# 22-eDP.net
KiCad netlist of a schematic drawn in Altium Designer
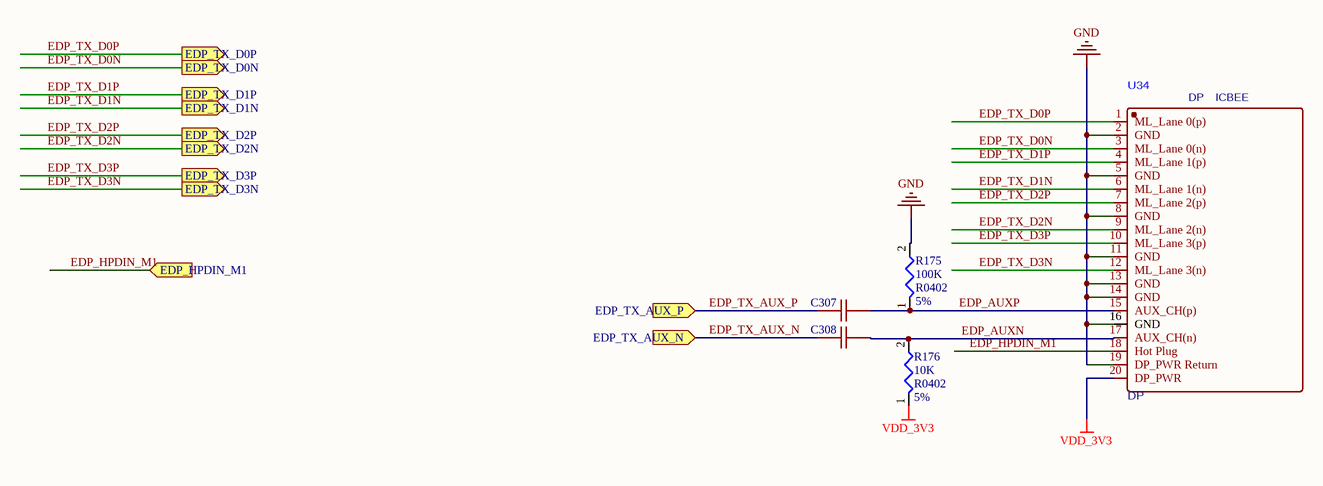
[diagram p0: 22-eDP.SchDoc]

(export (version "E")
  (design (tool "Eeschema 10.0.6"))
  (components
    (comp (ref "C307")
      (value "100nF")
      (footprint "C0201")
      (description "容值:100nF;精度:±10%;额定电压:16V;材质(温度系数):X5R;")
      (fields
        (field (name "MANUFACTURER") "SAMSUNG(三星)")
        (field (name "MANUFACTURER PART") "CL03A104KO3NNNC")
      )
      (libsource (lib "altium-import") (part "root_3_CL03A104KO3NNNC_"))
    )
    (comp (ref "C308")
      (value "100nF")
      (footprint "C0201")
      (description "容值:100nF;精度:±10%;额定电压:16V;材质(温度系数):X5R;")
      (fields
        (field (name "MANUFACTURER") "SAMSUNG(三星)")
        (field (name "MANUFACTURER PART") "CL03A104KO3NNNC")
      )
      (libsource (lib "altium-import") (part "root_3_CL03A104KO3NNNC_"))
    )
    (comp (ref "R175")
      (value "100K")
      (footprint "R0402")
      (description "通用厚膜电阻,10K,+/-5%,R0402,1/16W.")
      (fields
        (field (name "PCB FOOTPRINT") "R0402")
        (field (name "TOLERANCE") "5%")
        (field (name "MANUFACTURER") "YAGEO")
        (field (name "CREATED BY") "YTL")
      )
      (libsource (lib "*") (part "RESISTOR_Dup1"))
    )
    (comp (ref "R176")
      (value "10K")
      (footprint "R0402")
      (description "通用厚膜电阻,10K,+/-5%,R0402,1/16W.")
      (fields
        (field (name "PCB FOOTPRINT") "R0402")
        (field (name "TOLERANCE") "5%")
        (field (name "MANUFACTURER") "YAGEO")
        (field (name "CREATED BY") "YTL")
      )
      (libsource (lib "*") (part "RESISTOR_Dup1"))
    )
    (comp (ref "U34") (value "DP") (footprint "DP-ICBEE") (libsource (lib "RK3568核心板") (part "DP")))
  )
  (nets
    (net (code "1") (name "/EDP_AUXN") (class "Default")
      (node (ref "C308") (pin "2") (pinfunction "2_2") (pintype "passive"))
      (node (ref "R176") (pin "2") (pinfunction "2_2") (pintype "passive"))
      (node (ref "U34") (pin "17") (pinfunction "AUX_CH(n)_17") (pintype "passive"))
    )
    (net (code "2") (name "/EDP_AUXP") (class "Default")
      (node (ref "C307") (pin "2") (pinfunction "2_2") (pintype "passive"))
      (node (ref "R175") (pin "1") (pinfunction "1_1") (pintype "passive"))
      (node (ref "U34") (pin "15") (pinfunction "AUX_CH(p)_15") (pintype "passive"))
    )
    (net (code "3") (name "/EDP_HPDIN_M1") (class "Default")
      (node (ref "U34") (pin "18") (pinfunction "Hot_Plug_18") (pintype "passive"))
    )
    (net (code "4") (name "/EDP_TX_AUX_N") (class "Default")
      (node (ref "C308") (pin "1") (pinfunction "1_1") (pintype "passive"))
    )
    (net (code "5") (name "/EDP_TX_AUX_P") (class "Default")
      (node (ref "C307") (pin "1") (pinfunction "1_1") (pintype "passive"))
    )
    (net (code "6") (name "/EDP_TX_D0N") (class "Default")
      (node (ref "U34") (pin "3") (pinfunction "ML_Lane_0(n)_3") (pintype "passive"))
    )
    (net (code "7") (name "/EDP_TX_D0P") (class "Default")
      (node (ref "U34") (pin "1") (pinfunction "ML_Lane_0(p)_1") (pintype "passive"))
    )
    (net (code "8") (name "/EDP_TX_D1N") (class "Default")
      (node (ref "U34") (pin "6") (pinfunction "ML_Lane_1(n)_6") (pintype "passive"))
    )
    (net (code "9") (name "/EDP_TX_D1P") (class "Default")
      (node (ref "U34") (pin "4") (pinfunction "ML_Lane_1(p)_4") (pintype "passive"))
    )
    (net (code "10") (name "/EDP_TX_D2N") (class "Default")
      (node (ref "U34") (pin "9") (pinfunction "ML_Lane_2(n)_9") (pintype "passive"))
    )
    (net (code "11") (name "/EDP_TX_D2P") (class "Default")
      (node (ref "U34") (pin "7") (pinfunction "ML_Lane_2(p)_7") (pintype "passive"))
    )
    (net (code "12") (name "/EDP_TX_D3N") (class "Default")
      (node (ref "U34") (pin "12") (pinfunction "ML_Lane_3(n)_12") (pintype "passive"))
    )
    (net (code "13") (name "/EDP_TX_D3P") (class "Default")
      (node (ref "U34") (pin "10") (pinfunction "ML_Lane_3(p)_10") (pintype "passive"))
    )
    (net (code "14") (name "GND") (class "Default")
      (node (ref "R175") (pin "2") (pinfunction "2_2") (pintype "passive"))
      (node (ref "U34") (pin "11") (pinfunction "GND_11") (pintype "passive"))
      (node (ref "U34") (pin "13") (pinfunction "GND_13") (pintype "passive"))
      (node (ref "U34") (pin "14") (pinfunction "GND_14") (pintype "passive"))
      (node (ref "U34") (pin "16") (pinfunction "GND_16") (pintype "passive"))
      (node (ref "U34") (pin "19") (pinfunction "DP_PWR_Return_19") (pintype "passive"))
      (node (ref "U34") (pin "2") (pinfunction "GND_2") (pintype "passive"))
      (node (ref "U34") (pin "5") (pinfunction "GND_5") (pintype "passive"))
      (node (ref "U34") (pin "8") (pinfunction "GND_8") (pintype "passive"))
    )
    (net (code "15") (name "VDD_3V3") (class "Default")
      (node (ref "R176") (pin "1") (pinfunction "1_1") (pintype "passive"))
      (node (ref "U34") (pin "20") (pinfunction "DP_PWR_20") (pintype "passive"))
    )
  )
)
